# Potentiometer.net
KiCad netlist of a schematic drawn in EasyEDA
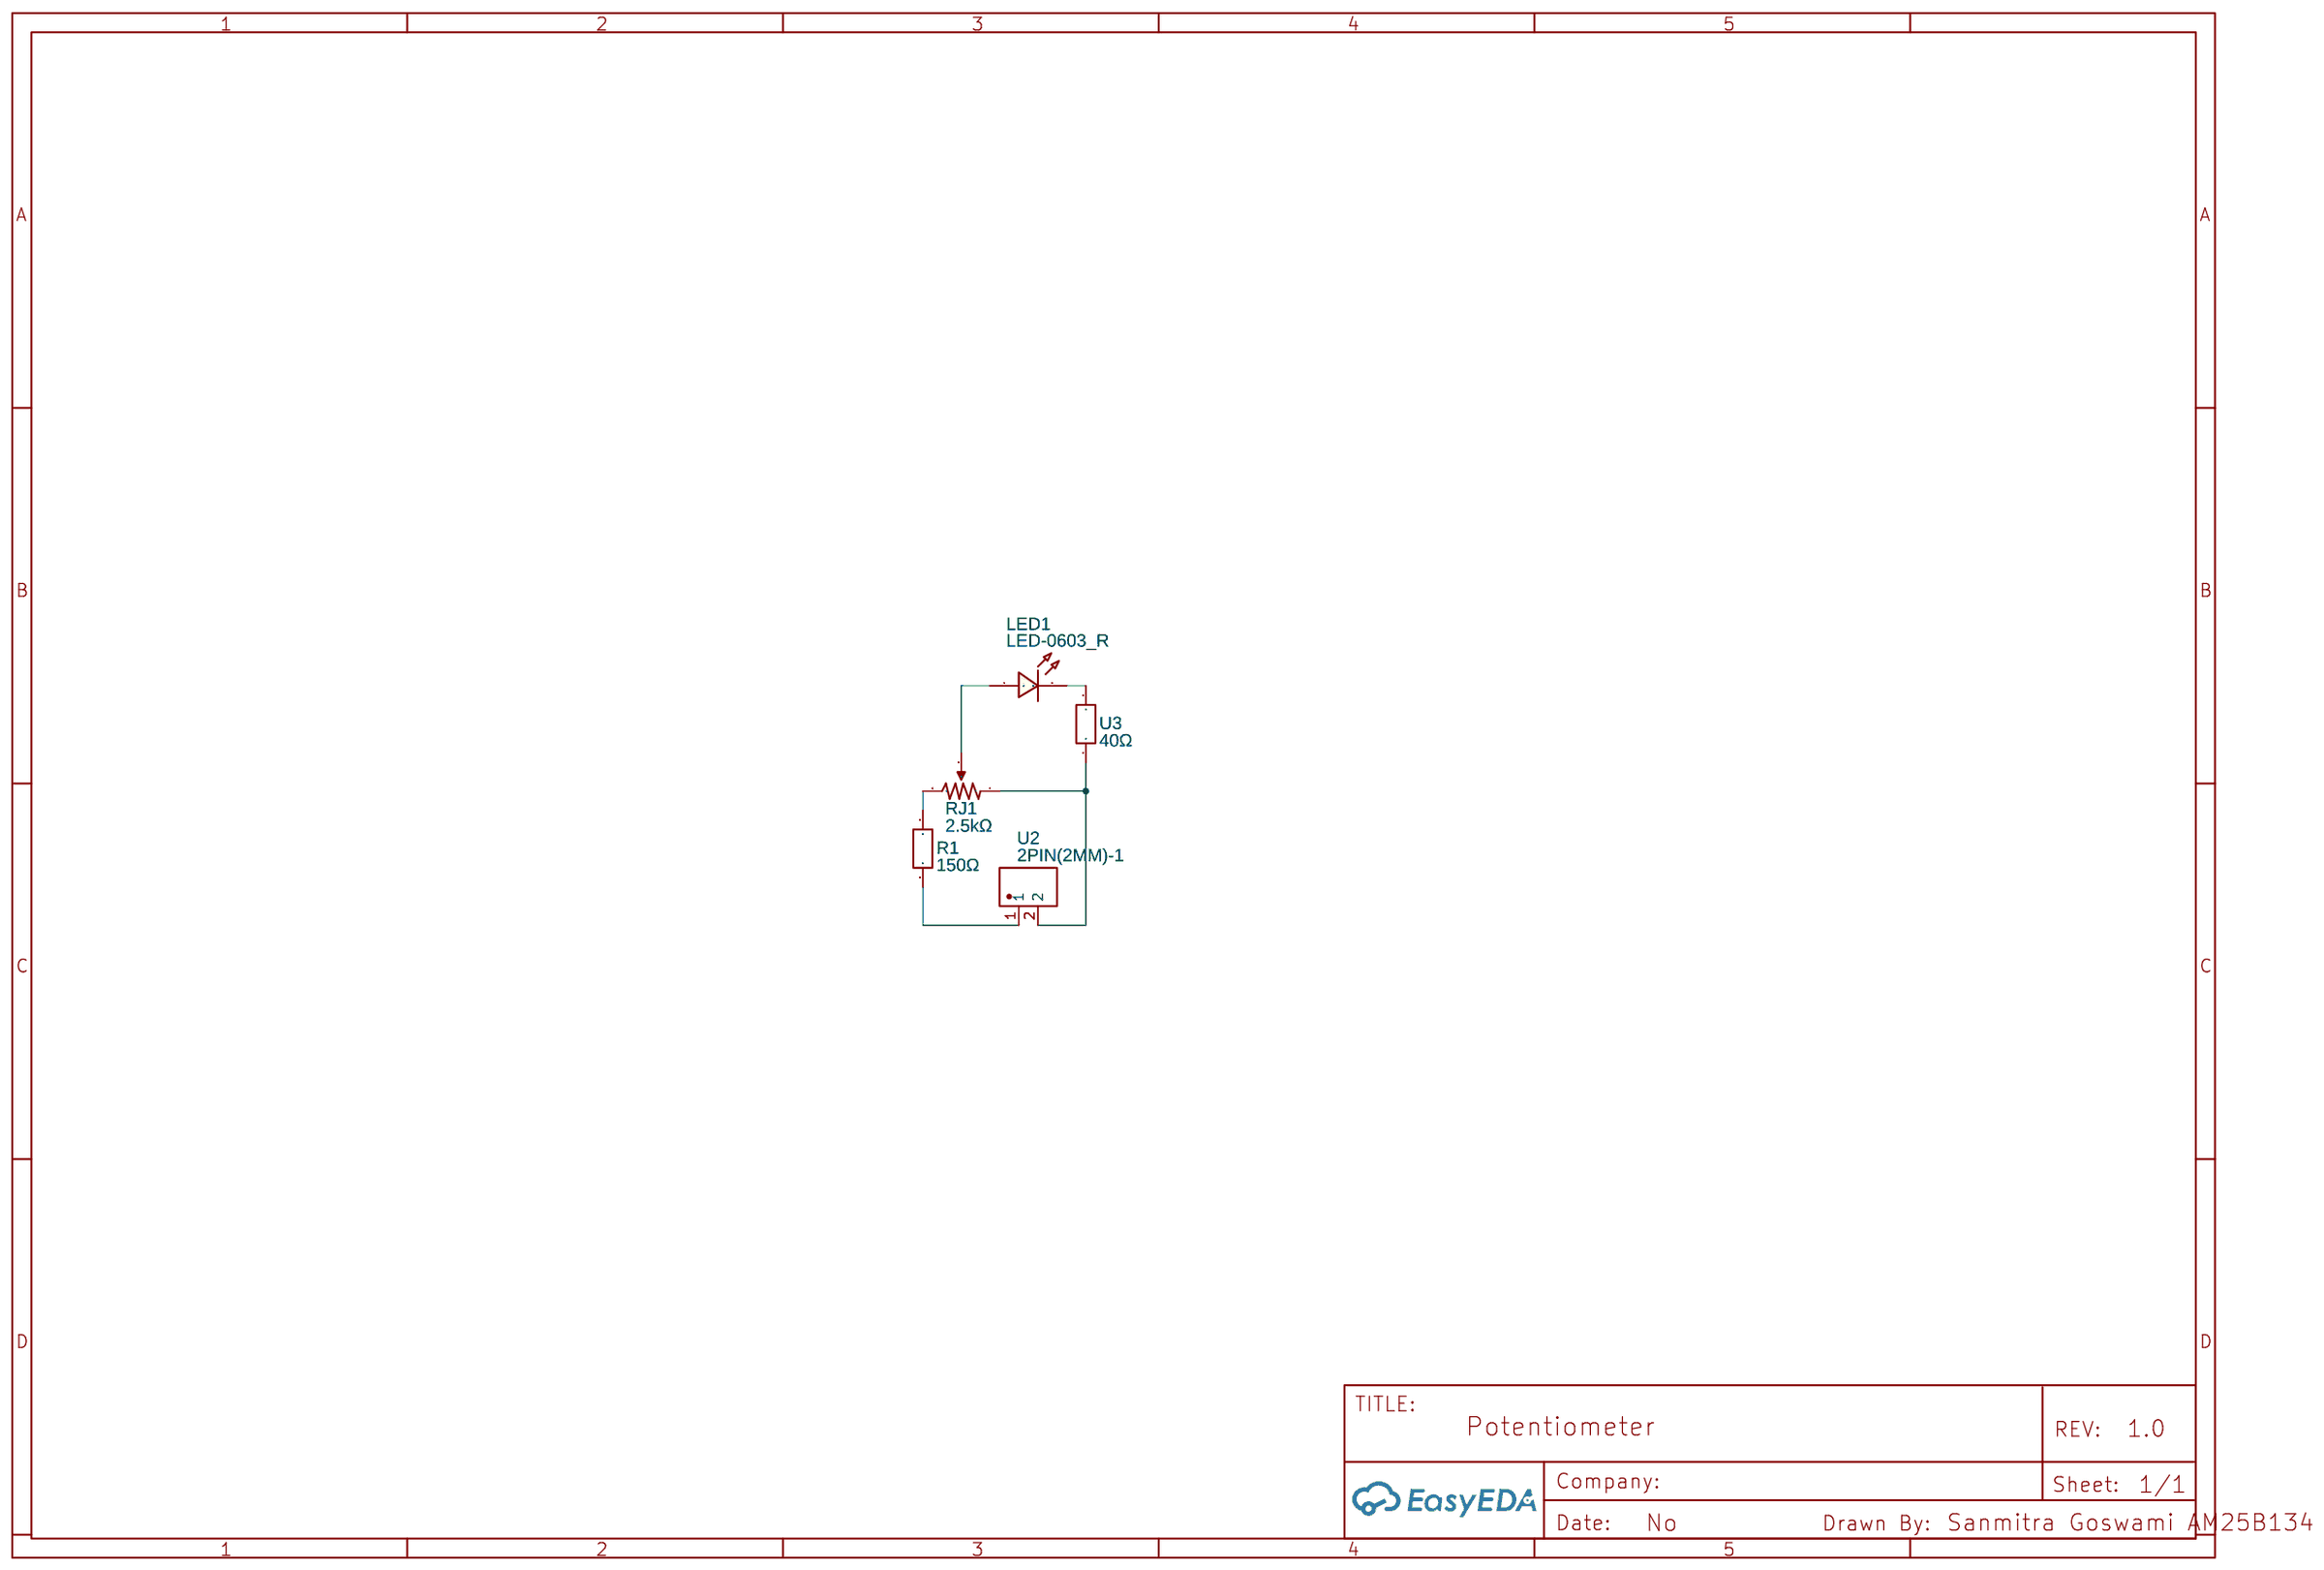
[diagram p0: schematic sheet]

(export (version "E")
  (design (tool "Eeschema 10.0.6"))
  (components
    (comp (ref "LED1")
      (value "LED-0603_R")
      (fields
        (field (name "Manufacturer Part") "19-217/R6C-AL1M2VY/3T")
        (field (name "Manufacturer") "EVERLIGHT(台湾亿光)")
      )
      (libsource (lib "") (part "LED-0603_R"))
    )
    (comp (ref "R1")
      (value "150Ω")
      (fields (field (name "Manufacturer Part") "CR1/8W-150Ω±5%-ST26") (field (name "Manufacturer") "VO(翔胜)"))
      (libsource (lib "") (part "CR1/8W-150Ω±5%-ST26"))
    )
    (comp (ref "RJ1")
      (value "2.5kΩ")
      (fields (field (name "Manufacturer Part") "3386P-1-252LF") (field (name "Manufacturer") "BOURNS"))
      (libsource (lib "") (part "3386P-1-252LF"))
    )
    (comp (ref "U2") (value "2PIN(2MM)-1") (libsource (lib "") (part "2PIN(2MM)-1")))
    (comp (ref "U3")
      (value "40Ω")
      (fields (field (name "Manufacturer Part") "R5J40RE") (field (name "Manufacturer") "Ohmite"))
      (libsource (lib "") (part "R5J40RE"))
    )
  )
  (nets
    (net (code "1") (name "Net-(LED1-Pad1)") (class "Default")
      (node (ref "LED1") (pin "1") (pinfunction "1_1") (pintype "unspecified"))
      (node (ref "RJ1") (pin "2") (pinfunction "2_2") (pintype "unspecified"))
    )
    (net (code "2") (name "Net-(LED1-Pad2)") (class "Default")
      (node (ref "LED1") (pin "2") (pinfunction "2_2") (pintype "unspecified"))
      (node (ref "U3") (pin "2") (pinfunction "2_2") (pintype "unspecified"))
    )
    (net (code "3") (name "Net-(R1-Pad1)") (class "Default")
      (node (ref "R1") (pin "1") (pinfunction "1_1") (pintype "unspecified"))
      (node (ref "U2") (pin "1") (pinfunction "1_1") (pintype "unspecified"))
    )
    (net (code "4") (name "Net-(R1-Pad2)") (class "Default")
      (node (ref "R1") (pin "2") (pinfunction "2_2") (pintype "unspecified"))
      (node (ref "RJ1") (pin "3") (pinfunction "3_3") (pintype "unspecified"))
    )
    (net (code "5") (name "Net-(RJ1-Pad1)") (class "Default")
      (node (ref "RJ1") (pin "1") (pinfunction "1_1") (pintype "unspecified"))
      (node (ref "U2") (pin "2") (pinfunction "2_2") (pintype "unspecified"))
      (node (ref "U3") (pin "1") (pinfunction "1_1") (pintype "unspecified"))
    )
  )
)
